# Buck_Regulator.net
KiCad netlist of a schematic drawn in EAGLE
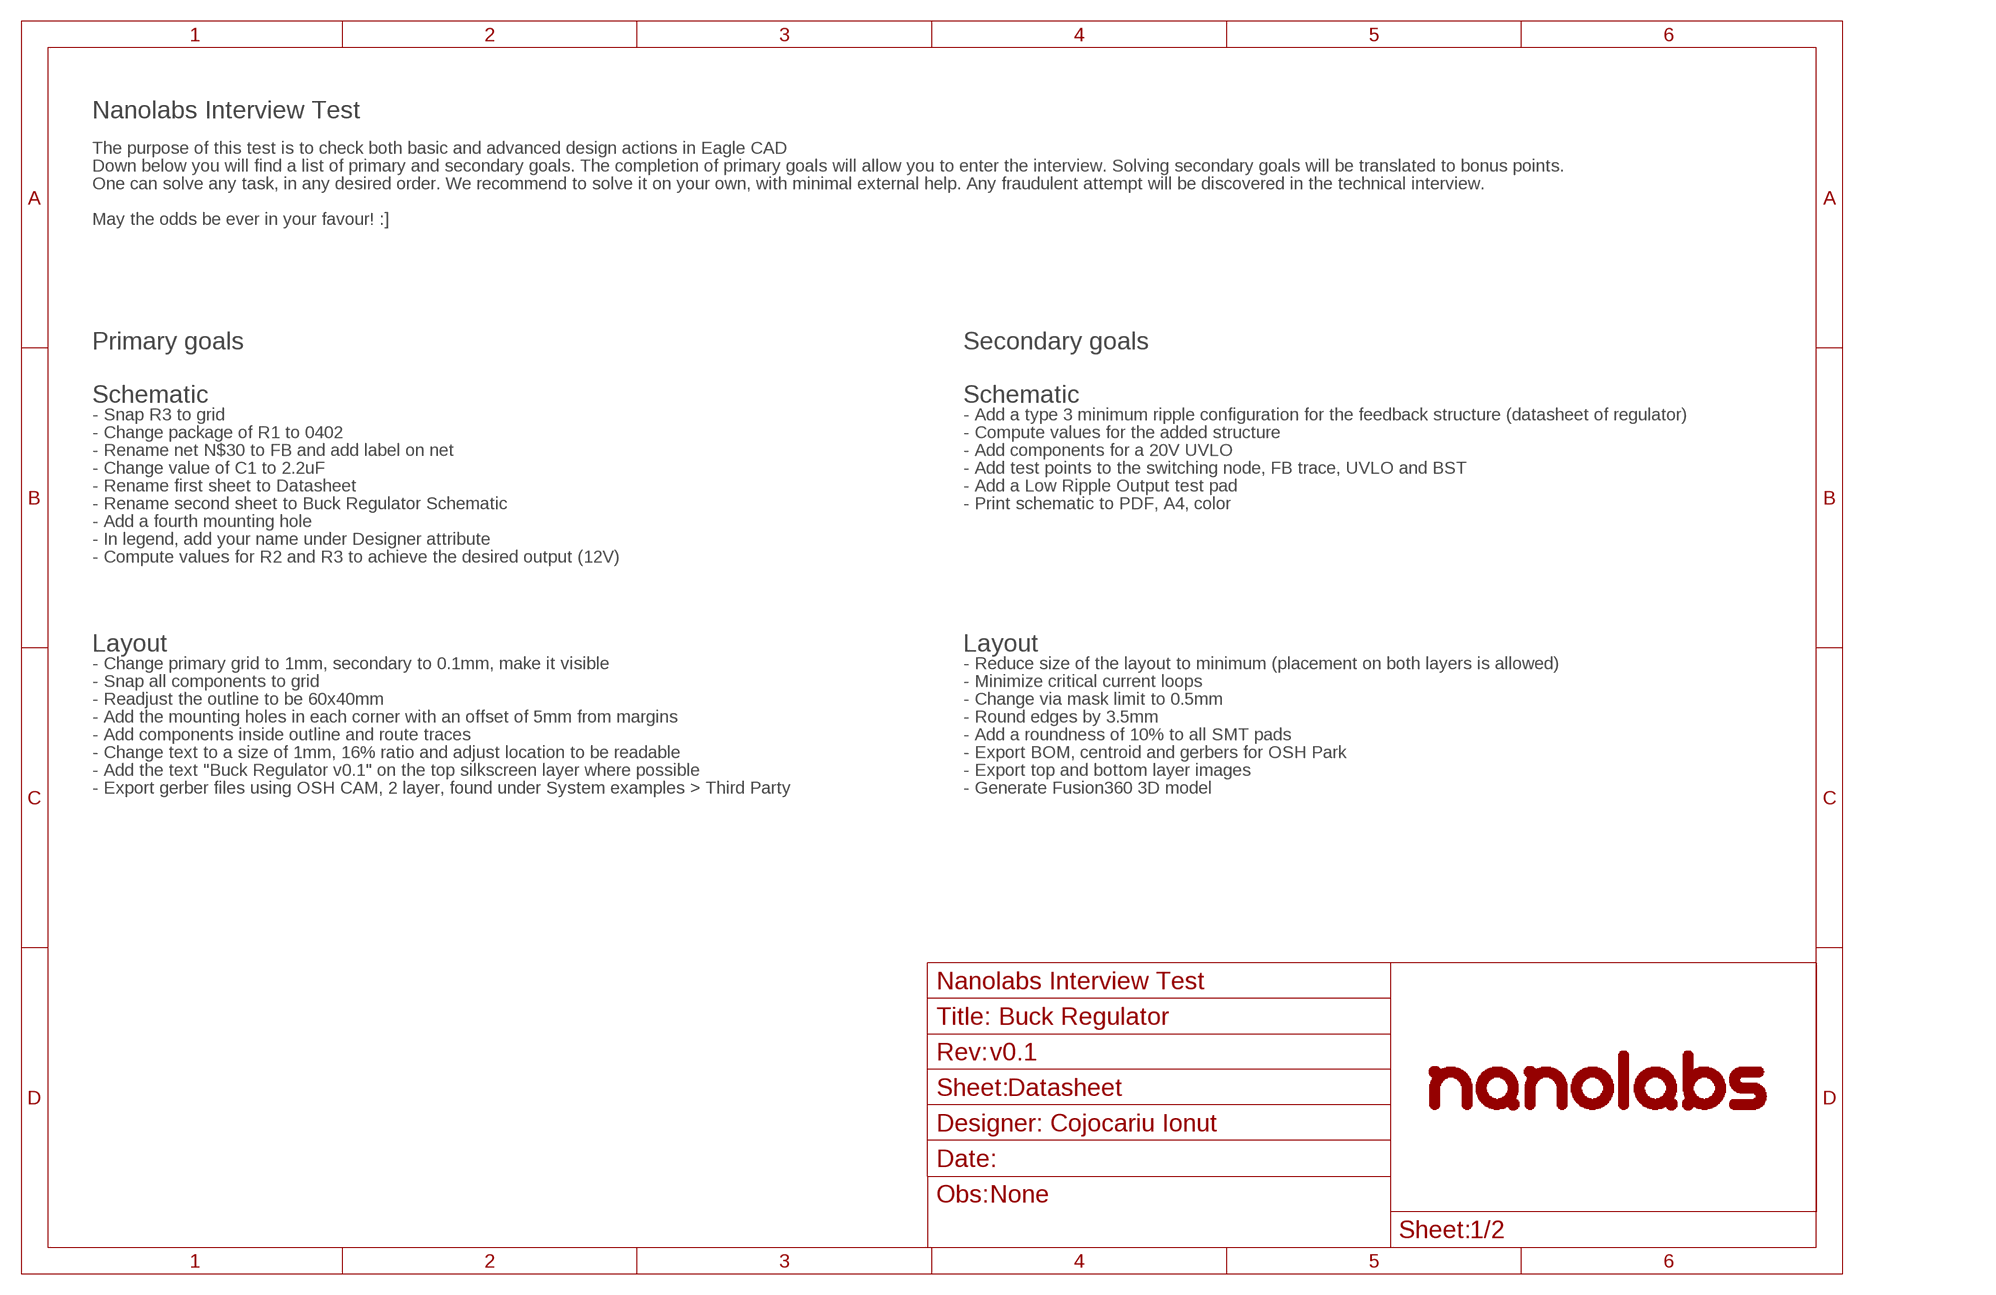
[diagram p0: schematic, sheet 1]
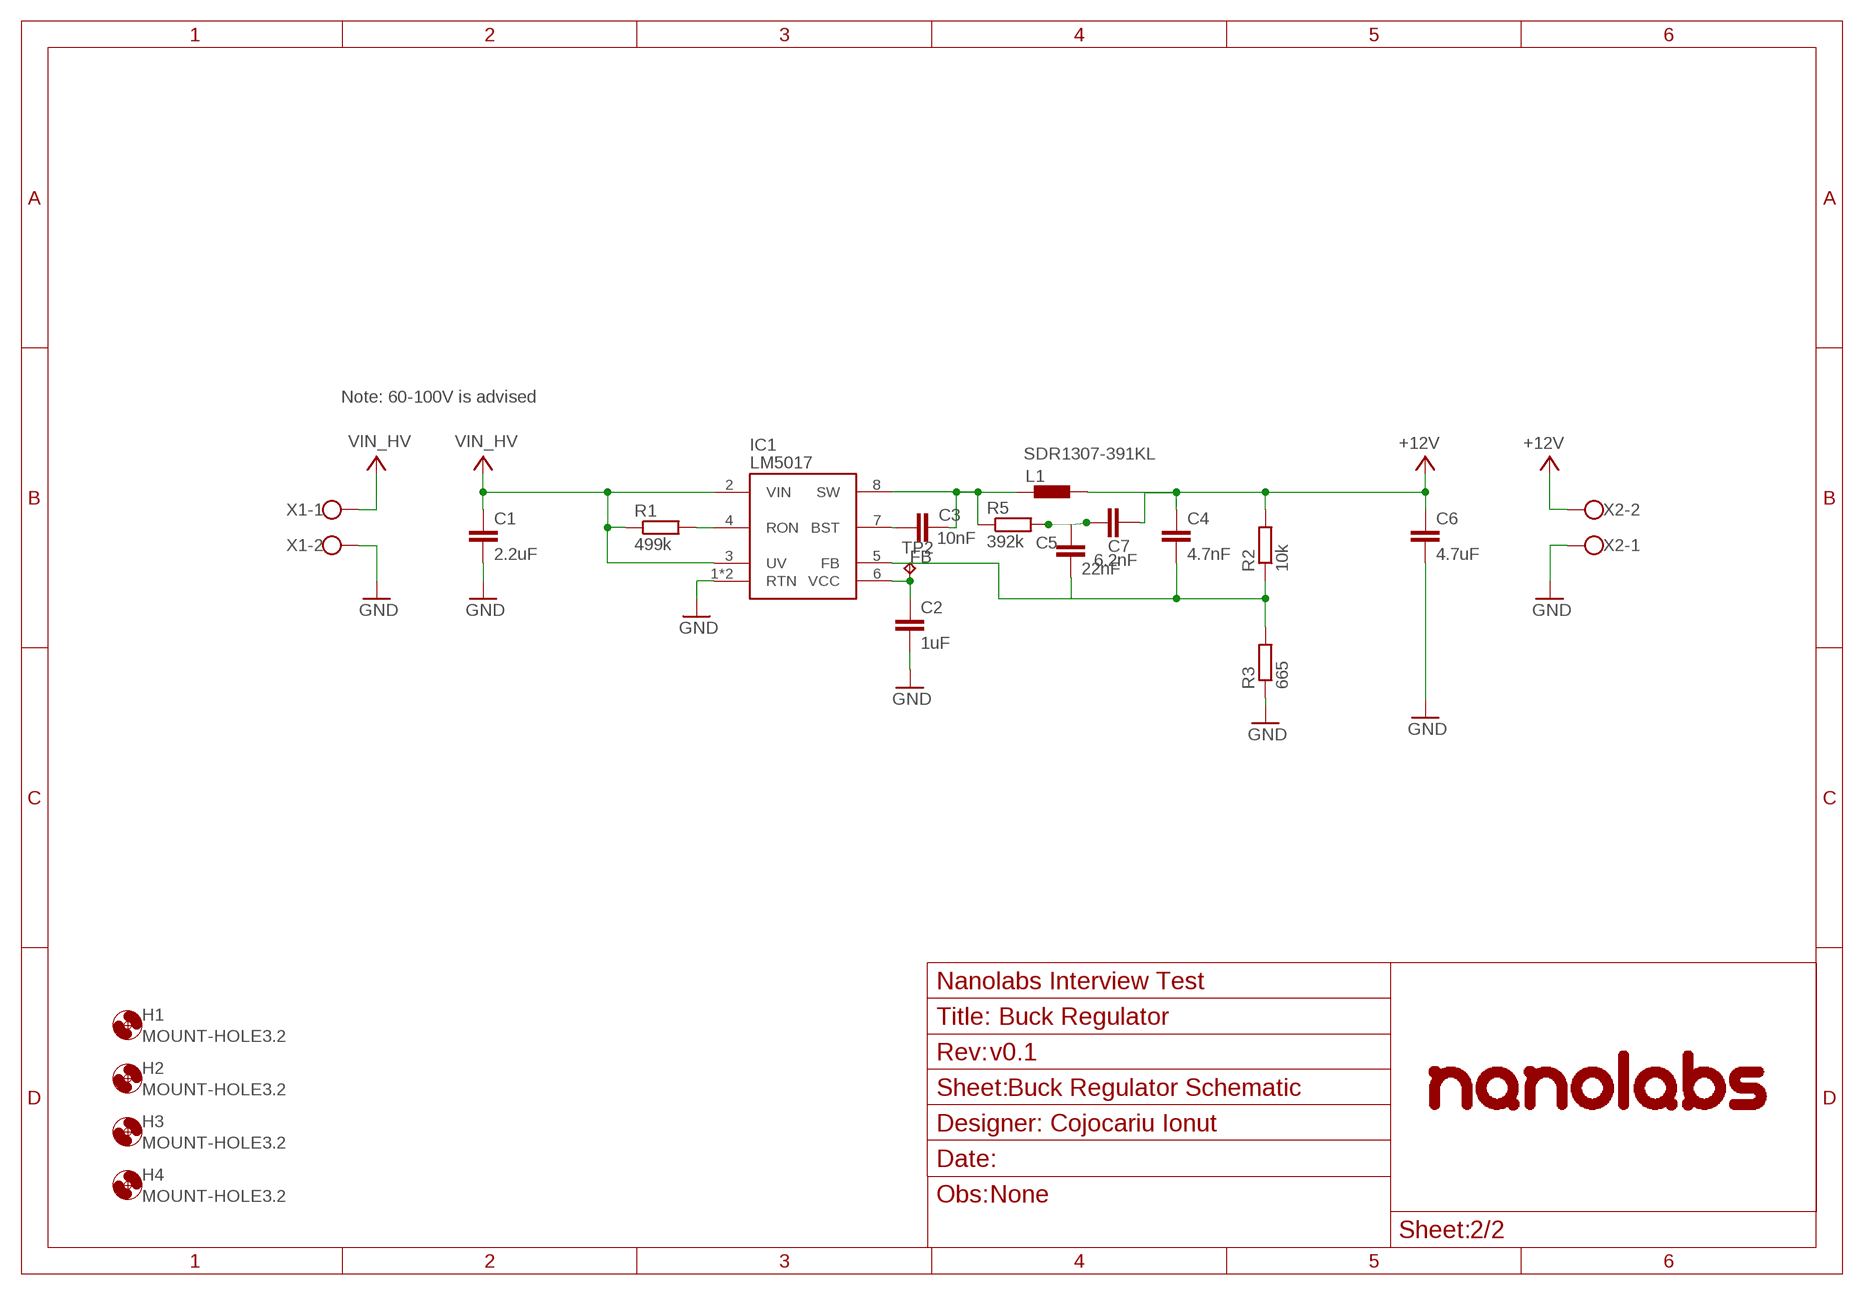
[diagram p1: schematic, sheet 2]

(export (version "E")
  (design (tool "Eeschema 10.0.6"))
  (components
    (comp (ref "C1")
      (value "2.2uF")
      (footprint "eagle-import:C1812")
      (libsource (lib "eagle-import") (part "C-EUC1812"))
    )
    (comp (ref "C2")
      (value "1uF")
      (footprint "eagle-import:C0603")
      (libsource (lib "eagle-import") (part "C-EUC0603"))
    )
    (comp (ref "C3")
      (value "10nF")
      (footprint "eagle-import:C0603")
      (libsource (lib "eagle-import") (part "C-EUC0603"))
    )
    (comp (ref "C4")
      (value "4.7nF")
      (footprint "eagle-import:C0603")
      (libsource (lib "eagle-import") (part "C-EUC0603"))
    )
    (comp (ref "C5")
      (value "22nF")
      (footprint "eagle-import:C2.5-2")
      (libsource (lib "eagle-import") (part "C2.5/2"))
    )
    (comp (ref "C6")
      (value "4.7uF")
      (footprint "eagle-import:C0603")
      (libsource (lib "eagle-import") (part "C-EUC0603"))
    )
    (comp (ref "C7")
      (value "6.2nF")
      (footprint "eagle-import:C2.5-2")
      (libsource (lib "eagle-import") (part "C2.5/2"))
    )
    (comp (ref "H1")
      (value "MOUNT-HOLE3.2")
      (footprint "eagle-import:3,2")
      (libsource (lib "eagle-import") (part "MOUNT-HOLE3.2"))
    )
    (comp (ref "H2")
      (value "MOUNT-HOLE3.2")
      (footprint "eagle-import:3,2")
      (libsource (lib "eagle-import") (part "MOUNT-HOLE3.2"))
    )
    (comp (ref "H3")
      (value "MOUNT-HOLE3.2")
      (footprint "eagle-import:3,2")
      (libsource (lib "eagle-import") (part "MOUNT-HOLE3.2"))
    )
    (comp (ref "H4")
      (value "MOUNT-HOLE3.2")
      (footprint "eagle-import:3,2")
      (libsource (lib "eagle-import") (part "holes_237_MOUNT-HOLE3.2"))
    )
    (comp (ref "IC1")
      (value "LM5017")
      (footprint "eagle-import:SO-08-EP")
      (libsource (lib "eagle-import") (part "LM5017"))
    )
    (comp (ref "L1")
      (value "SDR1307-391KL")
      (footprint "eagle-import:SDR1307-391KL")
      (libsource (lib "eagle-import") (part "SDR1307-391KL"))
    )
    (comp (ref "R1")
      (value "499k")
      (footprint "eagle-import:R0402")
      (libsource (lib "eagle-import") (part "R-EU_R0402"))
    )
    (comp (ref "R2")
      (value "10k")
      (footprint "eagle-import:R0603")
      (libsource (lib "eagle-import") (part "R-EU_R0603"))
    )
    (comp (ref "R3")
      (value "665")
      (footprint "eagle-import:R0603")
      (libsource (lib "eagle-import") (part "R-EU_R0603"))
    )
    (comp (ref "R5")
      (value "392k")
      (footprint "eagle-import:R0603")
      (libsource (lib "eagle-import") (part "R-EU_R0603"))
    )
    (comp (ref "TP2")
      (value "TPB1,27")
      (footprint "eagle-import:B1,27")
      (libsource (lib "eagle-import") (part "TPB1,27"))
    )
    (comp (ref "X1")
      (value "W237-102")
      (footprint "eagle-import:W237-102")
      (fields (field (name "MPN") "237-102"))
      (libsource (lib "eagle-import") (part "W237-102"))
    )
    (comp (ref "X2")
      (value "W237-102")
      (footprint "eagle-import:W237-102")
      (fields (field (name "MPN") "237-102"))
      (libsource (lib "eagle-import") (part "W237-102"))
    )
  )
  (nets
    (net (code "1") (name "+12V") (class "Default")
      (node (ref "C4") (pin "1") (pinfunction "1_1") (pintype "passive"))
      (node (ref "C6") (pin "1") (pinfunction "1_1") (pintype "passive"))
      (node (ref "C7") (pin "2") (pinfunction "2_2") (pintype "passive"))
      (node (ref "L1") (pin "2") (pinfunction "2_2") (pintype "passive"))
      (node (ref "R2") (pin "2") (pinfunction "2_2") (pintype "passive"))
      (node (ref "X2") (pin "2") (pinfunction "KL_2") (pintype "passive"))
    )
    (net (code "2") (name "FB") (class "Default")
      (node (ref "C4") (pin "2") (pinfunction "2_2") (pintype "passive"))
      (node (ref "C5") (pin "2") (pinfunction "2_2") (pintype "passive"))
      (node (ref "IC1") (pin "5") (pinfunction "FB_5") (pintype "bidirectional"))
      (node (ref "R2") (pin "1") (pinfunction "1_1") (pintype "passive"))
      (node (ref "R3") (pin "2") (pinfunction "2_2") (pintype "passive"))
    )
    (net (code "3") (name "GND") (class "Default")
      (node (ref "C1") (pin "2") (pinfunction "2_2") (pintype "passive"))
      (node (ref "C2") (pin "2") (pinfunction "2_2") (pintype "passive"))
      (node (ref "C6") (pin "2") (pinfunction "2_2") (pintype "passive"))
      (node (ref "IC1") (pin "1") (pinfunction "RTN_1") (pintype "bidirectional"))
      (node (ref "IC1") (pin "9") (pinfunction "RTN_9") (pintype "bidirectional"))
      (node (ref "R3") (pin "1") (pinfunction "1_1") (pintype "passive"))
      (node (ref "X1") (pin "2") (pinfunction "KL_2") (pintype "passive"))
      (node (ref "X2") (pin "1") (pinfunction "KL_1") (pintype "passive"))
    )
    (net (code "4") (name "Net-(C5-Pad1)") (class "Default")
      (node (ref "C5") (pin "1") (pinfunction "1_1") (pintype "passive"))
      (node (ref "C7") (pin "1") (pinfunction "1_1") (pintype "passive"))
      (node (ref "R5") (pin "2") (pinfunction "2_2") (pintype "passive"))
    )
    (net (code "5") (name "Net-(IC1-BST)") (class "Default")
      (node (ref "C3") (pin "1") (pinfunction "1_1") (pintype "passive"))
      (node (ref "IC1") (pin "7") (pinfunction "BST_7") (pintype "bidirectional"))
    )
    (net (code "6") (name "Net-(IC1-RON)") (class "Default")
      (node (ref "IC1") (pin "4") (pinfunction "RON_4") (pintype "bidirectional"))
      (node (ref "R1") (pin "2") (pinfunction "2_2") (pintype "passive"))
    )
    (net (code "7") (name "Net-(IC1-SW)") (class "Default")
      (node (ref "C3") (pin "2") (pinfunction "2_2") (pintype "passive"))
      (node (ref "IC1") (pin "8") (pinfunction "SW_8") (pintype "bidirectional"))
      (node (ref "L1") (pin "1") (pinfunction "1_1") (pintype "passive"))
      (node (ref "R5") (pin "1") (pinfunction "1_1") (pintype "passive"))
    )
    (net (code "8") (name "Net-(IC1-VCC)") (class "Default")
      (node (ref "C2") (pin "1") (pinfunction "1_1") (pintype "passive"))
      (node (ref "IC1") (pin "6") (pinfunction "VCC_6") (pintype "bidirectional"))
      (node (ref "TP2") (pin "TP") (pinfunction "TP_TP") (pintype "input"))
    )
    (net (code "9") (name "VIN_HV") (class "Default")
      (node (ref "C1") (pin "1") (pinfunction "1_1") (pintype "passive"))
      (node (ref "IC1") (pin "2") (pinfunction "VIN_2") (pintype "bidirectional"))
      (node (ref "IC1") (pin "3") (pinfunction "UV_3") (pintype "bidirectional"))
      (node (ref "R1") (pin "1") (pinfunction "1_1") (pintype "passive"))
      (node (ref "X1") (pin "1") (pinfunction "KL_1") (pintype "passive"))
    )
  )
)
